# Misc.net
KiCad netlist of a schematic drawn in Altium Designer
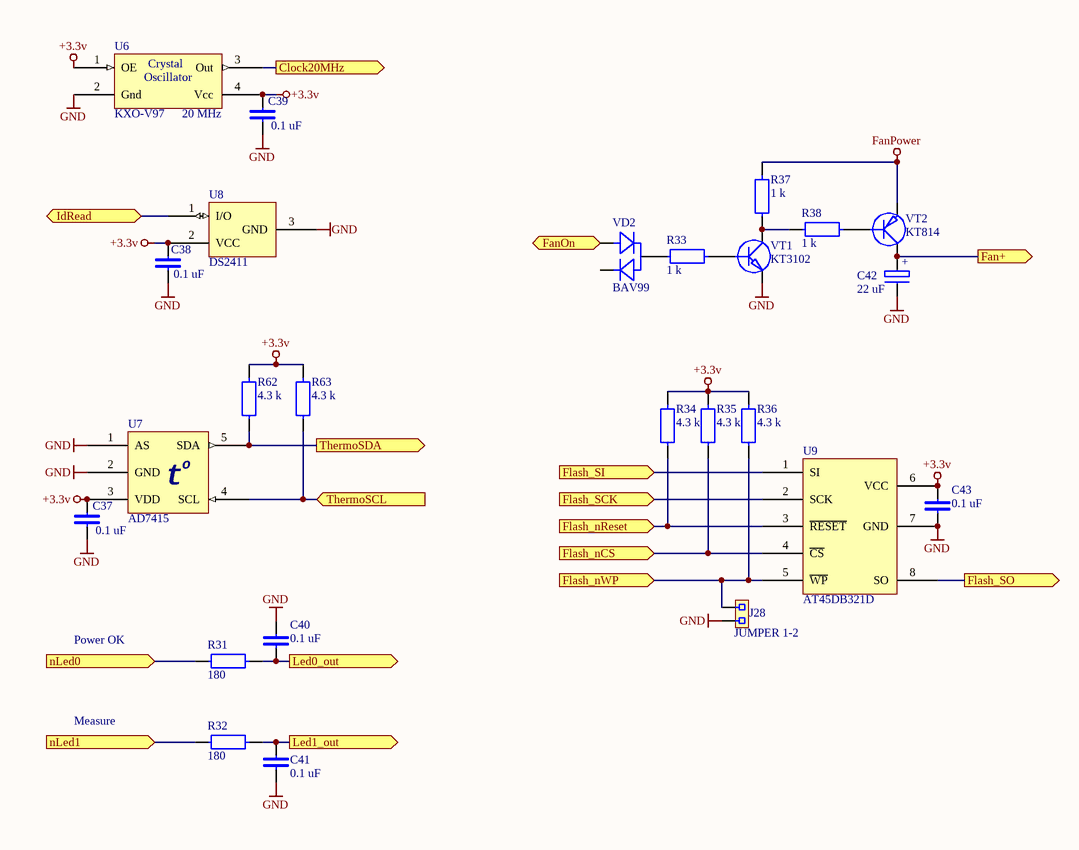
[diagram p0: Misc.SchDoc]

(export (version "E")
  (design (tool "Eeschema 10.0.6"))
  (components
    (comp (ref "C37") (value "0.1 uF") (footprint "0603") (libsource (lib "*") (part "C")))
    (comp (ref "C38") (value "0.1 uF") (footprint "0603") (libsource (lib "*") (part "C")))
    (comp (ref "C39") (value "0.1 uF") (footprint "1206") (libsource (lib "*") (part "C")))
    (comp (ref "C40") (value "0.1 uF") (footprint "1206") (libsource (lib "*") (part "C")))
    (comp (ref "C41") (value "0.1 uF") (footprint "1206") (libsource (lib "*") (part "C")))
    (comp (ref "C42") (value "22 uF") (footprint "CP6032") (libsource (lib "*") (part "C POL")))
    (comp (ref "C43") (value "0.1 uF") (footprint "0603") (libsource (lib "*") (part "C")))
    (comp (ref "J28")
      (value "JUMPER 1-2")
      (footprint "2SIP")
      (description "2.54 mm jumper")
      (libsource (lib "AConnectors") (part "JUMPER 1-2"))
    )
    (comp (ref "R31") (value "180") (footprint "0805") (libsource (lib "*") (part "R")))
    (comp (ref "R32") (value "180") (footprint "0805") (libsource (lib "*") (part "R")))
    (comp (ref "R33") (value "1 k") (footprint "1206") (libsource (lib "*") (part "R")))
    (comp (ref "R34") (value "4.3 k") (footprint "0603") (libsource (lib "*") (part "R")))
    (comp (ref "R35") (value "4.3 k") (footprint "0603") (libsource (lib "*") (part "R")))
    (comp (ref "R36") (value "4.3 k") (footprint "0603") (libsource (lib "*") (part "R")))
    (comp (ref "R37") (value "1 k") (footprint "1206") (libsource (lib "*") (part "R")))
    (comp (ref "R38") (value "1 k") (footprint "1206") (libsource (lib "*") (part "R")))
    (comp (ref "R62") (value "4.3 k") (footprint "0603") (libsource (lib "*") (part "R")))
    (comp (ref "R63") (value "4.3 k") (footprint "0603") (libsource (lib "*") (part "R")))
    (comp (ref "U6")
      (value "KXO-V97")
      (footprint "KXO-97")
      (description "Crystal Oscillator (SMD)")
      (libsource (lib "Mylib") (part "SG-636"))
    )
    (comp (ref "U7")
      (value "AD7415")
      (footprint "SOT-23-5")
      (description "10-Bit Digital Temperature Sensors")
      (libsource (lib "Mylib") (part "AD7415"))
    )
    (comp (ref "U8")
      (value "DS2411")
      (footprint "SOT-23")
      (description "Silicon Serial Number")
      (libsource (lib "Mylib") (part "DS2411"))
    )
    (comp (ref "U9")
      (value "AT45DB321D")
      (footprint "8SOIC208")
      (description "32 Mbit data flash memory")
      (libsource (lib "Mylib") (part "AT45DB321D"))
    )
    (comp (ref "VD2")
      (value "BAV99")
      (footprint "SOT-23")
      (description "Double diode")
      (libsource (lib "Vdiode") (part "BAV99"))
    )
    (comp (ref "VT1")
      (value "KT3102")
      (footprint "TRANS-KT3102M")
      (libsource (lib "Vtriode") (part "KT3102"))
    )
    (comp (ref "VT2") (value "KT814") (footprint "TRANS-KT814") (libsource (lib "Vtriode") (part "KT814")))
  )
  (nets
    (net (code "1") (name "+3.3v") (class "Default")
      (node (ref "C37") (pin "2") (pinfunction "2_2") (pintype "passive"))
      (node (ref "C38") (pin "2") (pinfunction "2_2") (pintype "passive"))
      (node (ref "C39") (pin "2") (pinfunction "2_2") (pintype "passive"))
      (node (ref "C43") (pin "1") (pinfunction "1_1") (pintype "passive"))
      (node (ref "R34") (pin "2") (pinfunction "2_2") (pintype "passive"))
      (node (ref "R35") (pin "2") (pinfunction "2_2") (pintype "passive"))
      (node (ref "R36") (pin "2") (pinfunction "2_2") (pintype "passive"))
      (node (ref "R62") (pin "2") (pinfunction "2_2") (pintype "passive"))
      (node (ref "R63") (pin "2") (pinfunction "2_2") (pintype "passive"))
      (node (ref "U6") (pin "1") (pinfunction "OE_1") (pintype "input"))
      (node (ref "U6") (pin "4") (pinfunction "Vcc_4") (pintype "passive"))
      (node (ref "U7") (pin "3") (pinfunction "VDD_3") (pintype "passive"))
      (node (ref "U8") (pin "2") (pinfunction "VCC_2") (pintype "passive"))
      (node (ref "U9") (pin "6") (pinfunction "VCC_6") (pintype "passive"))
    )
    (net (code "2") (name "/Clock20MHz") (class "Default")
      (node (ref "U6") (pin "3") (pinfunction "Out_3") (pintype "output"))
    )
    (net (code "3") (name "/Fan+") (class "Default")
      (node (ref "C42") (pin "+") (pinfunction "+_+") (pintype "passive"))
      (node (ref "VT2") (pin "COLL") (pinfunction "COLL_COLL") (pintype "passive"))
    )
    (net (code "4") (name "/FanOn") (class "Default")
      (node (ref "VD2") (pin "1") (pinfunction "1_1") (pintype "passive"))
    )
    (net (code "5") (name "/Flash_SCK") (class "Default")
      (node (ref "U9") (pin "2") (pinfunction "SCK_2") (pintype "passive"))
    )
    (net (code "6") (name "/Flash_SI") (class "Default")
      (node (ref "U9") (pin "1") (pinfunction "SI_1") (pintype "passive"))
    )
    (net (code "7") (name "/Flash_SO") (class "Default")
      (node (ref "U9") (pin "8") (pinfunction "SO_8") (pintype "passive"))
    )
    (net (code "8") (name "/Flash_nCS") (class "Default")
      (node (ref "R35") (pin "1") (pinfunction "1_1") (pintype "passive"))
      (node (ref "U9") (pin "4") (pinfunction "~{CS}_4") (pintype "passive"))
    )
    (net (code "9") (name "/Flash_nReset") (class "Default")
      (node (ref "R34") (pin "1") (pinfunction "1_1") (pintype "passive"))
      (node (ref "U9") (pin "3") (pinfunction "~{RESET}_3") (pintype "passive"))
    )
    (net (code "10") (name "/Flash_nWP") (class "Default")
      (node (ref "J28") (pin "1") (pinfunction "1_1") (pintype "passive"))
      (node (ref "R36") (pin "1") (pinfunction "1_1") (pintype "passive"))
      (node (ref "U9") (pin "5") (pinfunction "~{WP}_5") (pintype "passive"))
    )
    (net (code "11") (name "/IdRead") (class "Default")
      (node (ref "U8") (pin "1") (pinfunction "I/O_1") (pintype "bidirectional"))
    )
    (net (code "12") (name "/Led0_out") (class "Default")
      (node (ref "C40") (pin "2") (pinfunction "2_2") (pintype "passive"))
      (node (ref "R31") (pin "2") (pinfunction "2_2") (pintype "passive"))
    )
    (net (code "13") (name "/Led1_out") (class "Default")
      (node (ref "C41") (pin "1") (pinfunction "1_1") (pintype "passive"))
      (node (ref "R32") (pin "2") (pinfunction "2_2") (pintype "passive"))
    )
    (net (code "14") (name "/ThermoSCL") (class "Default")
      (node (ref "R63") (pin "1") (pinfunction "1_1") (pintype "passive"))
      (node (ref "U7") (pin "4") (pinfunction "SCL_4") (pintype "input"))
    )
    (net (code "15") (name "/ThermoSDA") (class "Default")
      (node (ref "R62") (pin "1") (pinfunction "1_1") (pintype "passive"))
      (node (ref "U7") (pin "5") (pinfunction "SDA_5") (pintype "output"))
    )
    (net (code "16") (name "/nLed0") (class "Default")
      (node (ref "R31") (pin "1") (pinfunction "1_1") (pintype "passive"))
    )
    (net (code "17") (name "/nLed1") (class "Default")
      (node (ref "R32") (pin "1") (pinfunction "1_1") (pintype "passive"))
    )
    (net (code "18") (name "FanPower") (class "Default")
      (node (ref "R37") (pin "2") (pinfunction "2_2") (pintype "passive"))
      (node (ref "VT2") (pin "EMIT") (pinfunction "EMIT_EMIT") (pintype "passive"))
    )
    (net (code "19") (name "GND") (class "Default")
      (node (ref "C37") (pin "1") (pinfunction "1_1") (pintype "passive"))
      (node (ref "C38") (pin "1") (pinfunction "1_1") (pintype "passive"))
      (node (ref "C39") (pin "1") (pinfunction "1_1") (pintype "passive"))
      (node (ref "C40") (pin "1") (pinfunction "1_1") (pintype "passive"))
      (node (ref "C41") (pin "2") (pinfunction "2_2") (pintype "passive"))
      (node (ref "C42") (pin "-") (pinfunction "-_-") (pintype "passive"))
      (node (ref "C43") (pin "2") (pinfunction "2_2") (pintype "passive"))
      (node (ref "J28") (pin "2") (pinfunction "2_2") (pintype "passive"))
      (node (ref "U6") (pin "2") (pinfunction "Gnd_2") (pintype "power_in"))
      (node (ref "U7") (pin "1") (pinfunction "AS_1") (pintype "passive"))
      (node (ref "U7") (pin "2") (pinfunction "GND_2") (pintype "passive"))
      (node (ref "U8") (pin "3") (pinfunction "GND_3") (pintype "passive"))
      (node (ref "U9") (pin "7") (pinfunction "GND_7") (pintype "passive"))
      (node (ref "VT1") (pin "EMIT") (pinfunction "EMIT_EMIT") (pintype "passive"))
    )
    (net (code "20") (name "Net-(R33-Pad1)") (class "Default")
      (node (ref "R33") (pin "1") (pinfunction "1_1") (pintype "passive"))
      (node (ref "VD2") (pin "3") (pinfunction "3_3") (pintype "passive"))
    )
    (net (code "21") (name "Net-(R33-Pad2)") (class "Default")
      (node (ref "R33") (pin "2") (pinfunction "2_2") (pintype "passive"))
      (node (ref "VT1") (pin "BASE") (pinfunction "BASE_BASE") (pintype "passive"))
    )
    (net (code "22") (name "Net-(R37-Pad1)") (class "Default")
      (node (ref "R37") (pin "1") (pinfunction "1_1") (pintype "passive"))
      (node (ref "R38") (pin "1") (pinfunction "1_1") (pintype "passive"))
      (node (ref "VT1") (pin "COLL") (pinfunction "COLL_COLL") (pintype "passive"))
    )
    (net (code "23") (name "Net-(R38-Pad2)") (class "Default")
      (node (ref "R38") (pin "2") (pinfunction "2_2") (pintype "passive"))
      (node (ref "VT2") (pin "BASE") (pinfunction "BASE_BASE") (pintype "passive"))
    )
    (net (code "24") (name "unconnected-(VD2-Pad2)") (class "Default")
      (node (ref "VD2") (pin "2") (pinfunction "2_2") (pintype "passive"))
    )
  )
)
